# Ver1_4.net
KiCad netlist of a schematic drawn in Altium Designer
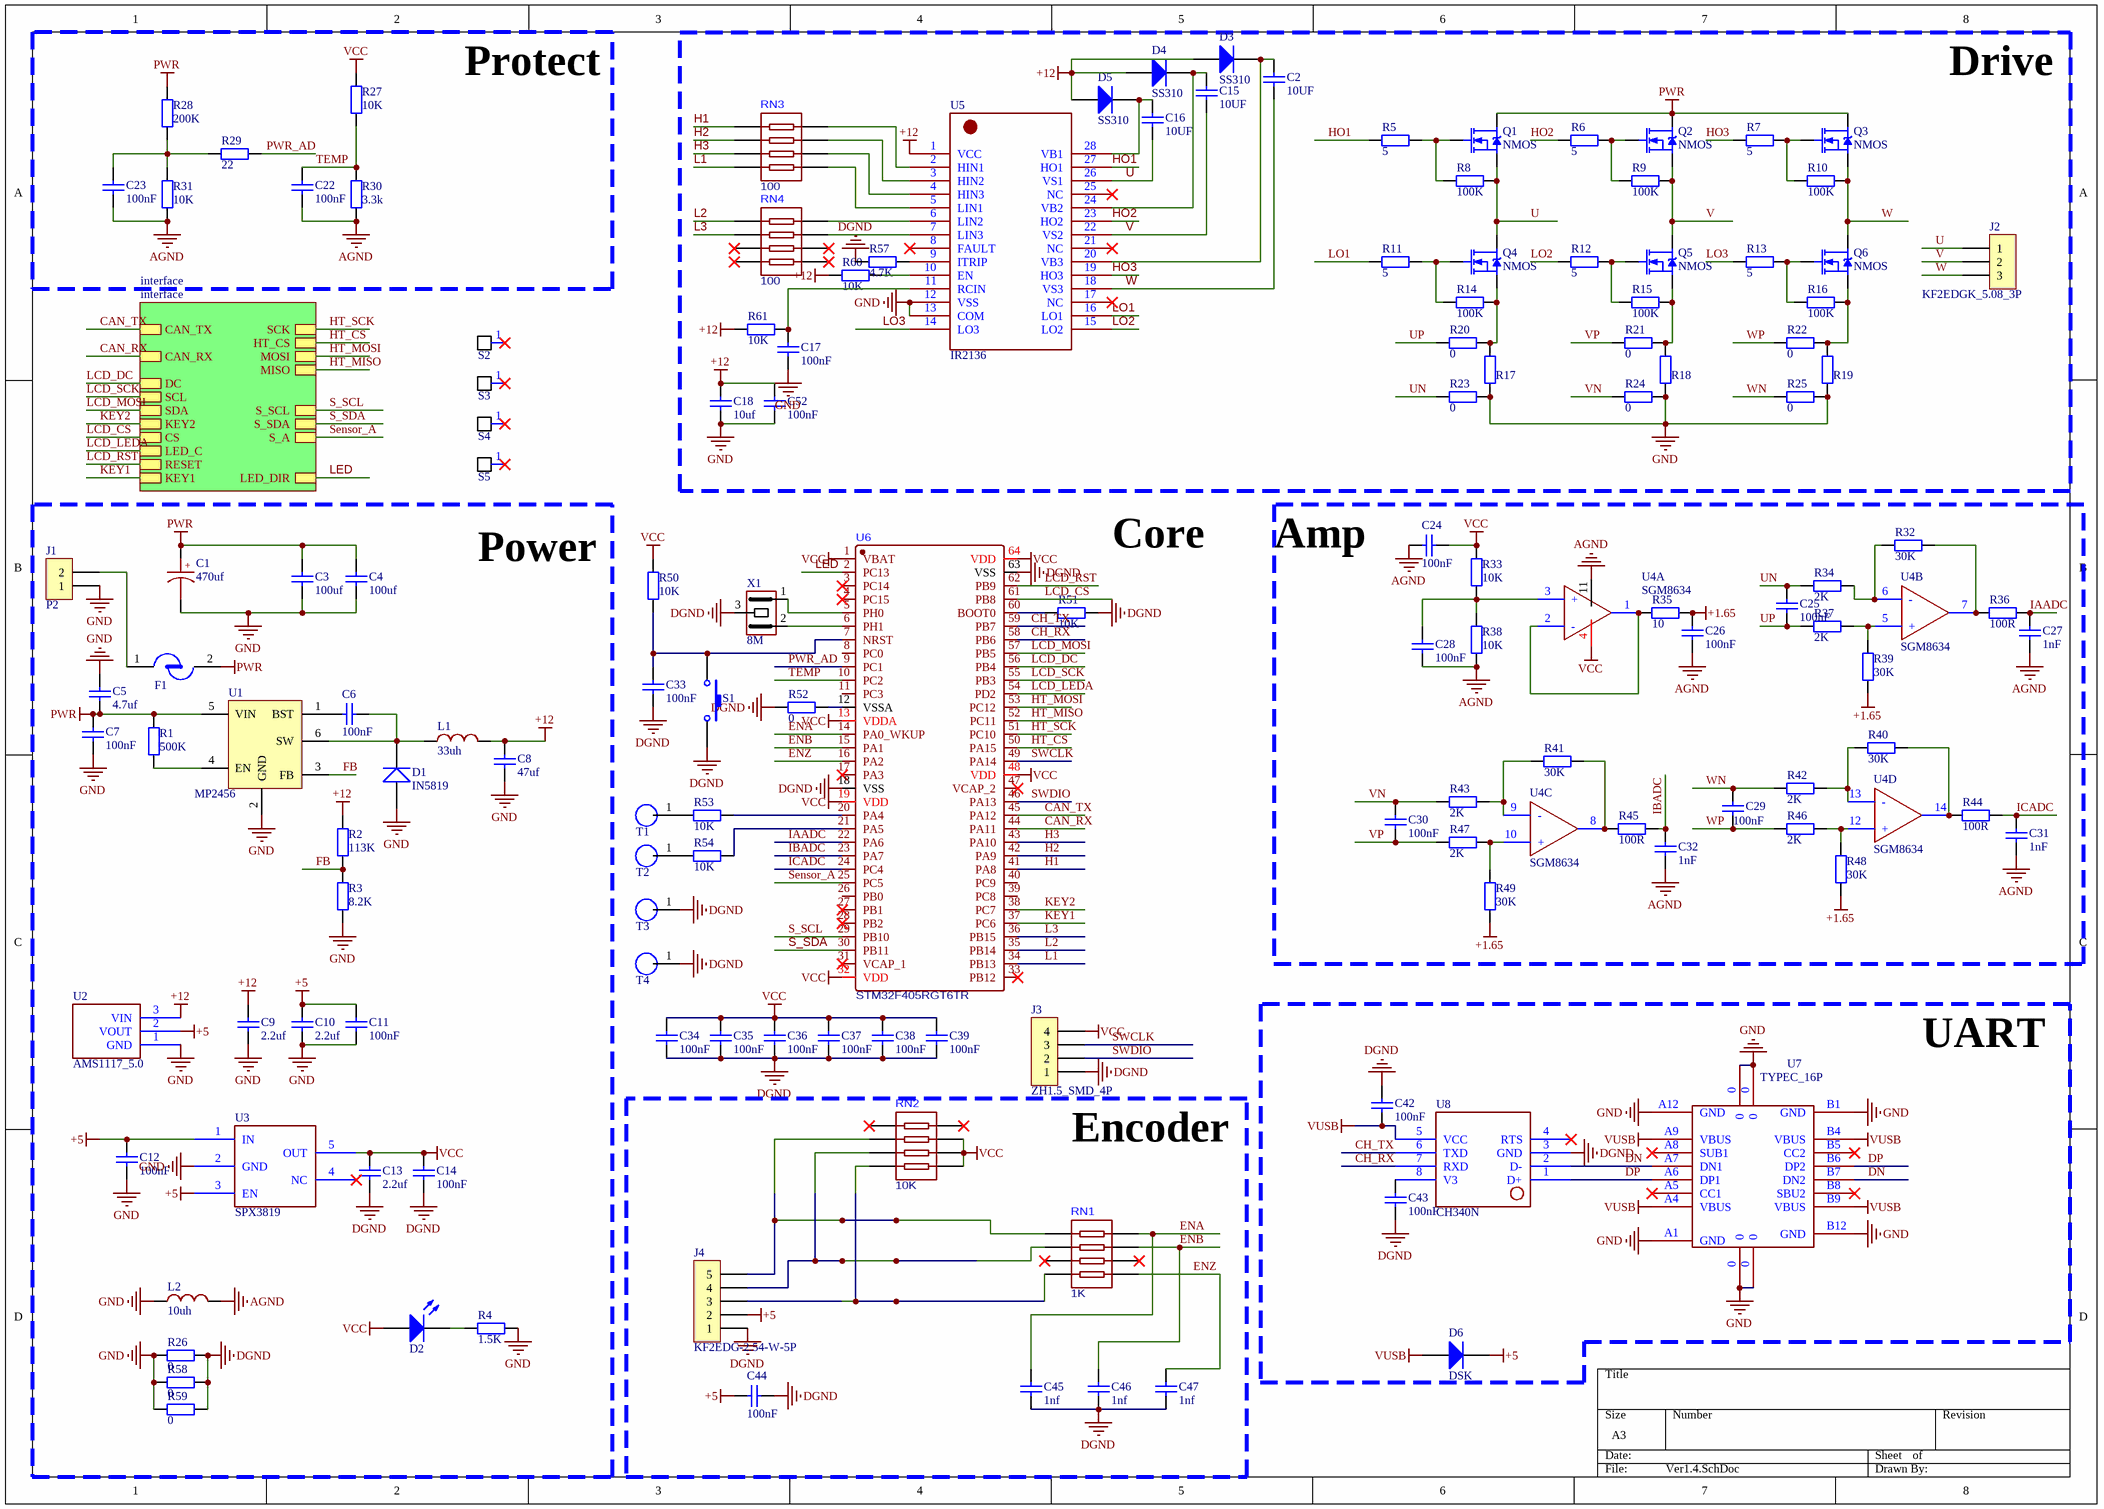
[diagram p0: Ver1.4.SchDoc]

(export (version "E")
  (design (tool "Eeschema 10.0.6"))
  (components
    (comp (ref "C1")
      (value "470uf")
      (footprint "CAP 5.0*12.5*20-H - BK")
      (description "CAP TH 330uf 13*25")
      (libsource (lib "CAP") (part "CAP_TH_D13"))
    )
    (comp (ref "C2")
      (value "10UF")
      (footprint "C 0603")
      (description "无极性电容")
      (fields (field (name "Comment") "Cap") (field (name "PUBLISHER") "Altium Limited"))
      (libsource (lib "CAP") (part "C0603"))
    )
    (comp (ref "C3")
      (value "100uf")
      (footprint "C 1210_L")
      (description "无极性电容")
      (fields (field (name "Comment") "Cap") (field (name "PUBLISHER") "Altium Limited"))
      (libsource (lib "CAP") (part "C1210"))
    )
    (comp (ref "C4")
      (value "100uf")
      (footprint "C 1210_L")
      (description "无极性电容")
      (fields (field (name "Comment") "Cap") (field (name "PUBLISHER") "Altium Limited"))
      (libsource (lib "CAP") (part "C1210"))
    )
    (comp (ref "C5")
      (value "4.7uf")
      (footprint "C 0402_L")
      (description "无极性电容")
      (fields (field (name "Comment") "Cap") (field (name "PUBLISHER") "Altium Limited"))
      (libsource (lib "CAP") (part "C0402"))
    )
    (comp (ref "C6")
      (value "100nF")
      (footprint "C 0402_L")
      (description "无极性电容")
      (fields (field (name "Comment") "Cap") (field (name "PUBLISHER") "Altium Limited"))
      (libsource (lib "CAP") (part "C0402"))
    )
    (comp (ref "C7")
      (value "100nF")
      (footprint "C 0402_L")
      (description "无极性电容")
      (fields (field (name "Comment") "Cap") (field (name "PUBLISHER") "Altium Limited"))
      (libsource (lib "CAP") (part "C0402"))
    )
    (comp (ref "C8")
      (value "47uf")
      (footprint "C 1206_L")
      (description "无极性电容")
      (fields (field (name "Comment") "Cap") (field (name "PUBLISHER") "Altium Limited"))
      (libsource (lib "CAP") (part "C1206"))
    )
    (comp (ref "C9")
      (value "2.2uf")
      (footprint "C 0402_L")
      (description "无极性电容")
      (fields (field (name "Comment") "Cap") (field (name "PUBLISHER") "Altium Limited"))
      (libsource (lib "CAP") (part "C0402"))
    )
    (comp (ref "C10")
      (value "2.2uf")
      (footprint "C 0402_L")
      (description "无极性电容")
      (fields (field (name "Comment") "Cap") (field (name "PUBLISHER") "Altium Limited"))
      (libsource (lib "CAP") (part "C0402"))
    )
    (comp (ref "C11")
      (value "100nF")
      (footprint "C 0402_L")
      (description "无极性电容")
      (fields (field (name "Comment") "Cap") (field (name "PUBLISHER") "Altium Limited"))
      (libsource (lib "CAP") (part "C0402"))
    )
    (comp (ref "C12")
      (value "100nF")
      (footprint "C 0402_L")
      (description "无极性电容")
      (fields (field (name "Comment") "Cap") (field (name "PUBLISHER") "Altium Limited"))
      (libsource (lib "CAP") (part "C0402"))
    )
    (comp (ref "C13")
      (value "2.2uf")
      (footprint "C 0402_L")
      (description "无极性电容")
      (fields (field (name "Comment") "Cap") (field (name "PUBLISHER") "Altium Limited"))
      (libsource (lib "CAP") (part "C0402"))
    )
    (comp (ref "C14")
      (value "100nF")
      (footprint "C 0402_L")
      (description "无极性电容")
      (fields (field (name "Comment") "Cap") (field (name "PUBLISHER") "Altium Limited"))
      (libsource (lib "CAP") (part "C0402"))
    )
    (comp (ref "C15")
      (value "10UF")
      (footprint "C 0603")
      (description "无极性电容")
      (fields (field (name "Comment") "Cap") (field (name "PUBLISHER") "Altium Limited"))
      (libsource (lib "CAP") (part "C0603"))
    )
    (comp (ref "C16")
      (value "10UF")
      (footprint "C 0603")
      (description "无极性电容")
      (fields (field (name "Comment") "Cap") (field (name "PUBLISHER") "Altium Limited"))
      (libsource (lib "CAP") (part "C0603"))
    )
    (comp (ref "C17")
      (value "100nF")
      (footprint "C 0402_L")
      (description "无极性电容")
      (fields (field (name "Comment") "Cap") (field (name "PUBLISHER") "Altium Limited"))
      (libsource (lib "CAP") (part "C0402"))
    )
    (comp (ref "C18")
      (value "10uf")
      (footprint "C 0603")
      (description "无极性电容")
      (fields (field (name "Comment") "Cap") (field (name "PUBLISHER") "Altium Limited"))
      (libsource (lib "CAP") (part "C0603"))
    )
    (comp (ref "C22")
      (value "100nF")
      (footprint "C 0402_L")
      (description "无极性电容")
      (fields (field (name "Comment") "Cap") (field (name "PUBLISHER") "Altium Limited"))
      (libsource (lib "CAP") (part "C0402"))
    )
    (comp (ref "C23")
      (value "100nF")
      (footprint "C 0402_L")
      (description "无极性电容")
      (fields (field (name "Comment") "Cap") (field (name "PUBLISHER") "Altium Limited"))
      (libsource (lib "CAP") (part "C0402"))
    )
    (comp (ref "C24")
      (value "100nF")
      (footprint "C 0402_L")
      (description "无极性电容")
      (fields (field (name "Comment") "Cap") (field (name "PUBLISHER") "Altium Limited"))
      (libsource (lib "CAP") (part "C0402"))
    )
    (comp (ref "C25")
      (value "100nF")
      (footprint "C 0402_L")
      (description "无极性电容")
      (fields (field (name "Comment") "Cap") (field (name "PUBLISHER") "Altium Limited"))
      (libsource (lib "CAP") (part "C0402"))
    )
    (comp (ref "C26")
      (value "100nF")
      (footprint "C 0402_L")
      (description "无极性电容")
      (fields (field (name "Comment") "Cap") (field (name "PUBLISHER") "Altium Limited"))
      (libsource (lib "CAP") (part "C0402"))
    )
    (comp (ref "C27")
      (value "1nF")
      (footprint "C 0402_L")
      (description "无极性电容")
      (fields (field (name "Comment") "Cap") (field (name "PUBLISHER") "Altium Limited"))
      (libsource (lib "CAP") (part "C0402"))
    )
    (comp (ref "C28")
      (value "100nF")
      (footprint "C 0402_L")
      (description "无极性电容")
      (fields (field (name "Comment") "Cap") (field (name "PUBLISHER") "Altium Limited"))
      (libsource (lib "CAP") (part "C0402"))
    )
    (comp (ref "C29")
      (value "100nF")
      (footprint "C 0402_L")
      (description "无极性电容")
      (fields (field (name "Comment") "Cap") (field (name "PUBLISHER") "Altium Limited"))
      (libsource (lib "CAP") (part "C0402"))
    )
    (comp (ref "C30")
      (value "100nF")
      (footprint "C 0402_L")
      (description "无极性电容")
      (fields (field (name "Comment") "Cap") (field (name "PUBLISHER") "Altium Limited"))
      (libsource (lib "CAP") (part "C0402"))
    )
    (comp (ref "C31")
      (value "1nF")
      (footprint "C 0402_L")
      (description "无极性电容")
      (fields (field (name "Comment") "Cap") (field (name "PUBLISHER") "Altium Limited"))
      (libsource (lib "CAP") (part "C0402"))
    )
    (comp (ref "C32")
      (value "1nF")
      (footprint "C 0402_L")
      (description "无极性电容")
      (fields (field (name "Comment") "Cap") (field (name "PUBLISHER") "Altium Limited"))
      (libsource (lib "CAP") (part "C0402"))
    )
    (comp (ref "C33")
      (value "100nF")
      (footprint "C 0402_L")
      (description "无极性电容")
      (fields (field (name "Comment") "Cap") (field (name "PUBLISHER") "Altium Limited"))
      (libsource (lib "CAP") (part "C0402"))
    )
    (comp (ref "C34")
      (value "100nF")
      (footprint "C 0402_L")
      (description "无极性电容")
      (fields (field (name "Comment") "Cap") (field (name "PUBLISHER") "Altium Limited"))
      (libsource (lib "CAP") (part "C0402"))
    )
    (comp (ref "C35")
      (value "100nF")
      (footprint "C 0402_L")
      (description "无极性电容")
      (fields (field (name "Comment") "Cap") (field (name "PUBLISHER") "Altium Limited"))
      (libsource (lib "CAP") (part "C0402"))
    )
    (comp (ref "C36")
      (value "100nF")
      (footprint "C 0402_L")
      (description "无极性电容")
      (fields (field (name "Comment") "Cap") (field (name "PUBLISHER") "Altium Limited"))
      (libsource (lib "CAP") (part "C0402"))
    )
    (comp (ref "C37")
      (value "100nF")
      (footprint "C 0402_L")
      (description "无极性电容")
      (fields (field (name "Comment") "Cap") (field (name "PUBLISHER") "Altium Limited"))
      (libsource (lib "CAP") (part "C0402"))
    )
    (comp (ref "C38")
      (value "100nF")
      (footprint "C 0402_L")
      (description "无极性电容")
      (fields (field (name "Comment") "Cap") (field (name "PUBLISHER") "Altium Limited"))
      (libsource (lib "CAP") (part "C0402"))
    )
    (comp (ref "C39")
      (value "100nF")
      (footprint "C 0402_L")
      (description "无极性电容")
      (fields (field (name "Comment") "Cap") (field (name "PUBLISHER") "Altium Limited"))
      (libsource (lib "CAP") (part "C0402"))
    )
    (comp (ref "C42")
      (value "100nF")
      (footprint "C 0402_L")
      (description "无极性电容")
      (fields (field (name "Comment") "Cap") (field (name "PUBLISHER") "Altium Limited"))
      (libsource (lib "CAP") (part "C0402"))
    )
    (comp (ref "C43")
      (value "100nF")
      (footprint "C 0402_L")
      (description "无极性电容")
      (fields (field (name "Comment") "Cap") (field (name "PUBLISHER") "Altium Limited"))
      (libsource (lib "CAP") (part "C0402"))
    )
    (comp (ref "C44")
      (value "100nF")
      (footprint "C 0402_L")
      (description "无极性电容")
      (fields (field (name "Comment") "Cap") (field (name "PUBLISHER") "Altium Limited"))
      (libsource (lib "CAP") (part "C0402"))
    )
    (comp (ref "C45")
      (value "1nf")
      (footprint "C 0402_L")
      (description "无极性电容")
      (fields (field (name "Comment") "Cap") (field (name "PUBLISHER") "Altium Limited"))
      (libsource (lib "CAP") (part "C0402"))
    )
    (comp (ref "C46")
      (value "1nf")
      (footprint "C 0402_L")
      (description "无极性电容")
      (fields (field (name "Comment") "Cap") (field (name "PUBLISHER") "Altium Limited"))
      (libsource (lib "CAP") (part "C0402"))
    )
    (comp (ref "C47")
      (value "1nf")
      (footprint "C 0402_L")
      (description "无极性电容")
      (fields (field (name "Comment") "Cap") (field (name "PUBLISHER") "Altium Limited"))
      (libsource (lib "CAP") (part "C0402"))
    )
    (comp (ref "C52")
      (value "100nF")
      (footprint "C 0402_L")
      (description "无极性电容")
      (fields (field (name "Comment") "Cap") (field (name "PUBLISHER") "Altium Limited"))
      (libsource (lib "CAP") (part "C0402"))
    )
    (comp (ref "D1")
      (value "IN5819")
      (footprint "SOD-323-12")
      (description "IN系列贴片")
      (fields (field (name "PUBLISHER") "mazhongwei"))
      (libsource (lib "晶体管") (part "DIO_SOD323"))
    )
    (comp (ref "D2")
      (value "LED")
      (footprint "LED0402-R-RD")
      (description "发光二极管")
      (fields (field (name "PUBLISHER") "Altium Limited"))
      (libsource (lib "晶体管") (part "LED0402"))
    )
    (comp (ref "D3")
      (value "SS310")
      (footprint "SMA/12")
      (description "SS系列")
      (fields (field (name "PUBLISHER") "mazhongwei"))
      (libsource (lib "晶体管") (part "DIO_SMA"))
    )
    (comp (ref "D4")
      (value "SS310")
      (footprint "SMA/12")
      (description "SS系列")
      (fields (field (name "PUBLISHER") "mazhongwei"))
      (libsource (lib "晶体管") (part "DIO_SMA"))
    )
    (comp (ref "D5")
      (value "SS310")
      (footprint "SMA/12")
      (description "SS系列")
      (fields (field (name "PUBLISHER") "mazhongwei"))
      (libsource (lib "晶体管") (part "DIO_SMA"))
    )
    (comp (ref "D6")
      (value "DSK")
      (footprint "SOD-123-PIN12")
      (description "DSK系列")
      (fields (field (name "PUBLISHER") "mazhongwei"))
      (libsource (lib "晶体管") (part "DIO_SOD123"))
    )
    (comp (ref "F1") (value "F0603") (footprint "FUSE-BLX-A") (libsource (lib "保险丝") (part "F0603")))
    (comp (ref "J1")
      (value "P2")
      (footprint "KF2EDGK5.08W-2P")
      (description "直插")
      (libsource (lib "接插件") (part "KF2EDGK_5.08_2P"))
    )
    (comp (ref "J2")
      (value "KF2EDGK_5.08_3P")
      (footprint "KF2EDGK5.08W-3P")
      (libsource (lib "接插件") (part "KF2EDGK_5.08_3P"))
    )
    (comp (ref "J3")
      (value "ZH1.5_SMD_4P")
      (footprint "ZH1.5-WS-4P")
      (libsource (lib "接插件") (part "ZH1.5_SMD_4P"))
    )
    (comp (ref "J4")
      (value "KF2EDG-2.54-W-5P")
      (footprint "KF2EDGK-2.54W-5P")
      (libsource (lib "接插件") (part "KF2EDG-2.54-W-5P"))
    )
    (comp (ref "L1")
      (value "33uh")
      (footprint "CD32")
      (description "功率贴片电感")
      (fields (field (name "PUBLISHER") "Altium Limited"))
      (libsource (lib "电感") (part "L0402"))
    )
    (comp (ref "L2")
      (value "10uh")
      (footprint "L 0805")
      (description "功率贴片电感")
      (fields (field (name "PUBLISHER") "Altium Limited"))
      (libsource (lib "电感") (part "L0402"))
    )
    (comp (ref "Q1")
      (value "NMOS")
      (footprint "TO252")
      (description "N沟道场效应管")
      (libsource (lib "晶体管") (part "NMOS"))
    )
    (comp (ref "Q2")
      (value "NMOS")
      (footprint "TO252")
      (description "N沟道场效应管")
      (libsource (lib "晶体管") (part "NMOS"))
    )
    (comp (ref "Q3")
      (value "NMOS")
      (footprint "TO252")
      (description "N沟道场效应管")
      (libsource (lib "晶体管") (part "NMOS"))
    )
    (comp (ref "Q4")
      (value "NMOS")
      (footprint "TO252")
      (description "N沟道场效应管")
      (libsource (lib "晶体管") (part "NMOS"))
    )
    (comp (ref "Q5")
      (value "NMOS")
      (footprint "TO252")
      (description "N沟道场效应管")
      (libsource (lib "晶体管") (part "NMOS"))
    )
    (comp (ref "Q6")
      (value "NMOS")
      (footprint "TO252")
      (description "N沟道场效应管")
      (libsource (lib "晶体管") (part "NMOS"))
    )
    (comp (ref "R1")
      (value "500K")
      (footprint "0402R")
      (description "贴片电阻")
      (fields (field (name "Comment") "Res1") (field (name "PUBLISHER") "Altium Limited"))
      (libsource (lib "") (part "R0402_1"))
    )
    (comp (ref "R2")
      (value "113K")
      (footprint "0402R")
      (description "贴片电阻")
      (fields (field (name "Comment") "Res1") (field (name "PUBLISHER") "Altium Limited"))
      (libsource (lib "") (part "R0402_1"))
    )
    (comp (ref "R3")
      (value "8.2K")
      (footprint "0402R")
      (description "贴片电阻")
      (fields (field (name "Comment") "Res1") (field (name "PUBLISHER") "Altium Limited"))
      (libsource (lib "") (part "R0402_1"))
    )
    (comp (ref "R4")
      (value "1.5K")
      (footprint "0402R")
      (description "贴片电阻")
      (fields (field (name "Comment") "Res1") (field (name "PUBLISHER") "Altium Limited"))
      (libsource (lib "RES") (part "R0402"))
    )
    (comp (ref "R5")
      (value "5")
      (footprint "0402R")
      (description "贴片电阻")
      (fields (field (name "Comment") "Res1") (field (name "PUBLISHER") "Altium Limited"))
      (libsource (lib "RES") (part "R0402"))
    )
    (comp (ref "R6")
      (value "5")
      (footprint "0402R")
      (description "贴片电阻")
      (fields (field (name "Comment") "Res1") (field (name "PUBLISHER") "Altium Limited"))
      (libsource (lib "RES") (part "R0402"))
    )
    (comp (ref "R7")
      (value "5")
      (footprint "0402R")
      (description "贴片电阻")
      (fields (field (name "Comment") "Res1") (field (name "PUBLISHER") "Altium Limited"))
      (libsource (lib "RES") (part "R0402"))
    )
    (comp (ref "R8")
      (value "100K")
      (footprint "0402R")
      (description "贴片电阻")
      (fields (field (name "Comment") "Res1") (field (name "PUBLISHER") "Altium Limited"))
      (libsource (lib "RES") (part "R0402"))
    )
    (comp (ref "R9")
      (value "100K")
      (footprint "0402R")
      (description "贴片电阻")
      (fields (field (name "Comment") "Res1") (field (name "PUBLISHER") "Altium Limited"))
      (libsource (lib "RES") (part "R0402"))
    )
    (comp (ref "R10")
      (value "100K")
      (footprint "0402R")
      (description "贴片电阻")
      (fields (field (name "Comment") "Res1") (field (name "PUBLISHER") "Altium Limited"))
      (libsource (lib "RES") (part "R0402"))
    )
    (comp (ref "R11")
      (value "5")
      (footprint "0402R")
      (description "贴片电阻")
      (fields (field (name "Comment") "Res1") (field (name "PUBLISHER") "Altium Limited"))
      (libsource (lib "RES") (part "R0402"))
    )
    (comp (ref "R12")
      (value "5")
      (footprint "0402R")
      (description "贴片电阻")
      (fields (field (name "Comment") "Res1") (field (name "PUBLISHER") "Altium Limited"))
      (libsource (lib "RES") (part "R0402"))
    )
    (comp (ref "R13")
      (value "5")
      (footprint "0402R")
      (description "贴片电阻")
      (fields (field (name "Comment") "Res1") (field (name "PUBLISHER") "Altium Limited"))
      (libsource (lib "RES") (part "R0402"))
    )
    (comp (ref "R14")
      (value "100K")
      (footprint "0402R")
      (description "贴片电阻")
      (fields (field (name "Comment") "Res1") (field (name "PUBLISHER") "Altium Limited"))
      (libsource (lib "RES") (part "R0402"))
    )
    (comp (ref "R15")
      (value "100K")
      (footprint "0402R")
      (description "贴片电阻")
      (fields (field (name "Comment") "Res1") (field (name "PUBLISHER") "Altium Limited"))
      (libsource (lib "RES") (part "R0402"))
    )
    (comp (ref "R16")
      (value "100K")
      (footprint "0402R")
      (description "贴片电阻")
      (fields (field (name "Comment") "Res1") (field (name "PUBLISHER") "Altium Limited"))
      (libsource (lib "RES") (part "R0402"))
    )
    (comp (ref "R17")
      (value "0.01")
      (footprint "2512R")
      (description "0.01采样电阻3W")
      (fields (field (name "PUBLISHER") "Altium Limited"))
      (libsource (lib "RES") (part "R2512"))
    )
    (comp (ref "R18")
      (value "0.01")
      (footprint "2512R")
      (description "0.01采样电阻3W")
      (fields (field (name "PUBLISHER") "Altium Limited"))
      (libsource (lib "RES") (part "R2512"))
    )
    (comp (ref "R19")
      (value "0.01")
      (footprint "2512R")
      (description "0.01采样电阻3W")
      (fields (field (name "PUBLISHER") "Altium Limited"))
      (libsource (lib "RES") (part "R2512"))
    )
    (comp (ref "R20")
      (value "0")
      (footprint "0402R")
      (description "贴片电阻")
      (fields (field (name "Comment") "Res1") (field (name "PUBLISHER") "Altium Limited"))
      (libsource (lib "RES") (part "R0402"))
    )
    (comp (ref "R21")
      (value "0")
      (footprint "0402R")
      (description "贴片电阻")
      (fields (field (name "Comment") "Res1") (field (name "PUBLISHER") "Altium Limited"))
      (libsource (lib "RES") (part "R0402"))
    )
    (comp (ref "R22")
      (value "0")
      (footprint "0402R")
      (description "贴片电阻")
      (fields (field (name "Comment") "Res1") (field (name "PUBLISHER") "Altium Limited"))
      (libsource (lib "RES") (part "R0402"))
    )
    (comp (ref "R23")
      (value "0")
      (footprint "0402R")
      (description "贴片电阻")
      (fields (field (name "Comment") "Res1") (field (name "PUBLISHER") "Altium Limited"))
      (libsource (lib "RES") (part "R0402"))
    )
    (comp (ref "R24")
      (value "0")
      (footprint "0402R")
      (description "贴片电阻")
      (fields (field (name "Comment") "Res1") (field (name "PUBLISHER") "Altium Limited"))
      (libsource (lib "RES") (part "R0402"))
    )
    (comp (ref "R25")
      (value "0")
      (footprint "0402R")
      (description "贴片电阻")
      (fields (field (name "Comment") "Res1") (field (name "PUBLISHER") "Altium Limited"))
      (libsource (lib "RES") (part "R0402"))
    )
    (comp (ref "R26")
      (value "0")
      (footprint "0402R")
      (description "贴片电阻")
      (fields (field (name "Comment") "Res1") (field (name "PUBLISHER") "Altium Limited"))
      (libsource (lib "RES") (part "R0402"))
    )
    (comp (ref "R27")
      (value "10K")
      (footprint "0402R")
      (description "贴片电阻")
      (fields (field (name "Comment") "Res1") (field (name "PUBLISHER") "Altium Limited"))
      (libsource (lib "") (part "R0402_1"))
    )
    (comp (ref "R28")
      (value "200K")
      (footprint "0402R")
      (description "贴片电阻")
      (fields (field (name "Comment") "Res1") (field (name "PUBLISHER") "Altium Limited"))
      (libsource (lib "") (part "R0402_1"))
    )
    (comp (ref "R29")
      (value "22")
      (footprint "0402R")
      (description "贴片电阻")
      (fields (field (name "Comment") "Res1") (field (name "PUBLISHER") "Altium Limited"))
      (libsource (lib "RES") (part "R0402"))
    )
    (comp (ref "R30")
      (value "3.3k")
      (footprint "0402R")
      (description "贴片电阻")
      (fields (field (name "Comment") "Res1") (field (name "PUBLISHER") "Altium Limited"))
      (libsource (lib "") (part "R0402_1"))
    )
    (comp (ref "R31")
      (value "10K")
      (footprint "0402R")
      (description "贴片电阻")
      (fields (field (name "Comment") "Res1") (field (name "PUBLISHER") "Altium Limited"))
      (libsource (lib "") (part "R0402_1"))
    )
    (comp (ref "R32")
      (value "30K")
      (footprint "0402R")
      (description "贴片电阻")
      (fields (field (name "Comment") "Res1") (field (name "PUBLISHER") "Altium Limited"))
      (libsource (lib "") (part "R0402_2"))
    )
    (comp (ref "R33")
      (value "10K")
      (footprint "0402R")
      (description "贴片电阻")
      (fields (field (name "Comment") "Res1") (field (name "PUBLISHER") "Altium Limited"))
      (libsource (lib "") (part "R0402_3"))
    )
    (comp (ref "R34")
      (value "2K")
      (footprint "0402R")
      (description "贴片电阻")
      (fields (field (name "Comment") "Res1") (field (name "PUBLISHER") "Altium Limited"))
      (libsource (lib "RES") (part "R0402"))
    )
    (comp (ref "R35")
      (value "10")
      (footprint "0402R")
      (description "贴片电阻")
      (fields (field (name "Comment") "Res1") (field (name "PUBLISHER") "Altium Limited"))
      (libsource (lib "RES") (part "R0402"))
    )
    (comp (ref "R36")
      (value "100R")
      (footprint "0402R")
      (description "贴片电阻")
      (fields (field (name "Comment") "Res1") (field (name "PUBLISHER") "Altium Limited"))
      (libsource (lib "") (part "R0402_2"))
    )
    (comp (ref "R37")
      (value "2K")
      (footprint "0402R")
      (description "贴片电阻")
      (fields (field (name "Comment") "Res1") (field (name "PUBLISHER") "Altium Limited"))
      (libsource (lib "RES") (part "R0402"))
    )
    (comp (ref "R38")
      (value "10K")
      (footprint "0402R")
      (description "贴片电阻")
      (fields (field (name "Comment") "Res1") (field (name "PUBLISHER") "Altium Limited"))
      (libsource (lib "") (part "R0402_3"))
    )
    (comp (ref "R39")
      (value "30K")
      (footprint "0402R")
      (description "贴片电阻")
      (fields (field (name "Comment") "Res1") (field (name "PUBLISHER") "Altium Limited"))
      (libsource (lib "") (part "R0402_1"))
    )
    (comp (ref "R40")
      (value "30K")
      (footprint "0402R")
      (description "贴片电阻")
      (fields (field (name "Comment") "Res1") (field (name "PUBLISHER") "Altium Limited"))
      (libsource (lib "") (part "R0402_2"))
    )
    (comp (ref "R41")
      (value "30K")
      (footprint "0402R")
      (description "贴片电阻")
      (fields (field (name "Comment") "Res1") (field (name "PUBLISHER") "Altium Limited"))
      (libsource (lib "") (part "R0402_2"))
    )
    (comp (ref "R42")
      (value "2K")
      (footprint "0402R")
      (description "贴片电阻")
      (fields (field (name "Comment") "Res1") (field (name "PUBLISHER") "Altium Limited"))
      (libsource (lib "RES") (part "R0402"))
    )
    (comp (ref "R43")
      (value "2K")
      (footprint "0402R")
      (description "贴片电阻")
      (fields (field (name "Comment") "Res1") (field (name "PUBLISHER") "Altium Limited"))
      (libsource (lib "RES") (part "R0402"))
    )
    (comp (ref "R44")
      (value "100R")
      (footprint "0402R")
      (description "贴片电阻")
      (fields (field (name "Comment") "Res1") (field (name "PUBLISHER") "Altium Limited"))
      (libsource (lib "") (part "R0402_2"))
    )
    (comp (ref "R45")
      (value "100R")
      (footprint "0402R")
      (description "贴片电阻")
      (fields (field (name "Comment") "Res1") (field (name "PUBLISHER") "Altium Limited"))
      (libsource (lib "") (part "R0402_2"))
    )
    (comp (ref "R46")
      (value "2K")
      (footprint "0402R")
      (description "贴片电阻")
      (fields (field (name "Comment") "Res1") (field (name "PUBLISHER") "Altium Limited"))
      (libsource (lib "RES") (part "R0402"))
    )
    (comp (ref "R47")
      (value "2K")
      (footprint "0402R")
      (description "贴片电阻")
      (fields (field (name "Comment") "Res1") (field (name "PUBLISHER") "Altium Limited"))
      (libsource (lib "RES") (part "R0402"))
    )
    (comp (ref "R48")
      (value "30K")
      (footprint "0402R")
      (description "贴片电阻")
      (fields (field (name "Comment") "Res1") (field (name "PUBLISHER") "Altium Limited"))
      (libsource (lib "") (part "R0402_1"))
    )
    (comp (ref "R49")
      (value "30K")
      (footprint "0402R")
      (description "贴片电阻")
      (fields (field (name "Comment") "Res1") (field (name "PUBLISHER") "Altium Limited"))
      (libsource (lib "") (part "R0402_1"))
    )
    (comp (ref "R50")
      (value "10K")
      (footprint "0402R")
      (description "贴片电阻")
      (fields (field (name "Comment") "Res1") (field (name "PUBLISHER") "Altium Limited"))
      (libsource (lib "") (part "R0402_1"))
    )
    (comp (ref "R51")
      (value "10K")
      (footprint "0402R")
      (description "贴片电阻")
      (fields (field (name "Comment") "Res1") (field (name "PUBLISHER") "Altium Limited"))
      (libsource (lib "RES") (part "R0402"))
    )
    (comp (ref "R52")
      (value "0")
      (footprint "0402R")
      (description "贴片电阻")
      (fields (field (name "Comment") "Res1") (field (name "PUBLISHER") "Altium Limited"))
      (libsource (lib "RES") (part "R0603"))
    )
    (comp (ref "R53")
      (value "10K")
      (footprint "0402R")
      (description "贴片电阻")
      (fields (field (name "Comment") "Res1") (field (name "PUBLISHER") "Altium Limited"))
      (libsource (lib "RES") (part "R0402"))
    )
    (comp (ref "R54")
      (value "10K")
      (footprint "0402R")
      (description "贴片电阻")
      (fields (field (name "Comment") "Res1") (field (name "PUBLISHER") "Altium Limited"))
      (libsource (lib "RES") (part "R0402"))
    )
    (comp (ref "R57")
      (value "4.7K")
      (footprint "0402R")
      (description "贴片电阻")
      (fields (field (name "Comment") "Res1") (field (name "PUBLISHER") "Altium Limited"))
      (libsource (lib "RES") (part "R0402"))
    )
    (comp (ref "R58")
      (value "0")
      (footprint "0402R")
      (description "贴片电阻")
      (fields (field (name "Comment") "Res1") (field (name "PUBLISHER") "Altium Limited"))
      (libsource (lib "RES") (part "R0402"))
    )
    (comp (ref "R59")
      (value "0")
      (footprint "0402R")
      (description "贴片电阻")
      (fields (field (name "Comment") "Res1") (field (name "PUBLISHER") "Altium Limited"))
      (libsource (lib "RES") (part "R0402"))
    )
    (comp (ref "R60")
      (value "10K")
      (footprint "0402R")
      (description "贴片电阻")
      (fields (field (name "Comment") "Res1") (field (name "PUBLISHER") "Altium Limited"))
      (libsource (lib "") (part "R0402_2"))
    )
    (comp (ref "R61")
      (value "10K")
      (footprint "0402R")
      (description "贴片电阻")
      (fields (field (name "Comment") "Res1") (field (name "PUBLISHER") "Altium Limited"))
      (libsource (lib "") (part "R0402_2"))
    )
    (comp (ref "RN1")
      (value "1K")
      (footprint "8P4R-0402")
      (description "0402排阻")
      (libsource (lib "RES") (part "RESP0402"))
    )
    (comp (ref "RN2")
      (value "10K")
      (footprint "8P4R-0402")
      (description "0402排阻")
      (libsource (lib "RES") (part "RESP0402"))
    )
    (comp (ref "RN3")
      (value "100")
      (footprint "8P4R-0402")
      (description "0402排阻")
      (libsource (lib "RES") (part "RESP0402"))
    )
    (comp (ref "RN4")
      (value "100")
      (footprint "8P4R-0402")
      (description "0402排阻")
      (libsource (lib "RES") (part "RESP0402"))
    )
    (comp (ref "S1")
      (value "SW-PB")
      (footprint "SMD-4X4X1.5")
      (description "贴片侧4脚按键")
      (fields (field (name "PUBLISHER") "Altium Limited"))
      (libsource (lib "KEY") (part "KEY_SMD_2*4*3.5"))
    )
    (comp (ref "S2")
      (value "M3")
      (footprint "3mm螺丝孔")
      (description "3mm螺丝孔")
      (libsource (lib "MCU") (part "M3"))
    )
    (comp (ref "S3")
      (value "M3")
      (footprint "3mm螺丝孔")
      (description "3mm螺丝孔")
      (libsource (lib "MCU") (part "M3"))
    )
    (comp (ref "S4")
      (value "M3")
      (footprint "3mm螺丝孔")
      (description "3mm螺丝孔")
      (libsource (lib "MCU") (part "M3"))
    )
    (comp (ref "S5")
      (value "M3")
      (footprint "3mm螺丝孔")
      (description "3mm螺丝孔")
      (libsource (lib "MCU") (part "M3"))
    )
    (comp (ref "T1")
      (value "TEST")
      (footprint "TEST_1mm")
      (description "测试点1mm")
      (libsource (lib "MCU") (part "TEST"))
    )
    (comp (ref "T2")
      (value "TEST")
      (footprint "TEST_1mm")
      (description "测试点1mm")
      (libsource (lib "MCU") (part "TEST"))
    )
    (comp (ref "T3")
      (value "TEST")
      (footprint "TEST_1mm")
      (description "测试点1mm")
      (libsource (lib "MCU") (part "TEST"))
    )
    (comp (ref "T4")
      (value "TEST")
      (footprint "TEST_1mm")
      (description "测试点1mm")
      (libsource (lib "MCU") (part "TEST"))
    )
    (comp (ref "U1") (value "MP2456") (footprint "SOT23-6L") (libsource (lib "MCU") (part "MP2456")))
    (comp (ref "U2")
      (value "AMS1117_5.0")
      (footprint "SOT89_M")
      (description "AMS1117-5V  SOT89   MAX24V")
      (libsource (lib "MCU") (part "AMS1117_5.0"))
    )
    (comp (ref "U3") (value "SPX3819") (footprint "SOT23-5L") (libsource (lib "MCU") (part "SPX3819")))
    (comp (ref "U4")
      (value "SGM8634")
      (footprint "SOP14_L")
      (description "TSSOP-14")
      (libsource (lib "MCU") (part "TL084CPWR"))
    )
    (comp (ref "U5") (value "IR2136") (footprint "SOP28_L") (libsource (lib "MCU") (part "IR2136")))
    (comp (ref "U6")
      (value "STM32F405RGT6TR")
      (footprint "LQFP64 10x10_M")
      (libsource (lib "MCU") (part "STM32F405RGT6TR"))
    )
    (comp (ref "U7") (value "TYPEC_16P") (footprint "TYPECP16") (libsource (lib "MCU") (part "TYPEC_16P")))
    (comp (ref "U8") (value "CH340N") (footprint "SOP8_N") (libsource (lib "MCU") (part "CH340N")))
    (comp (ref "X1")
      (value "8M")
      (footprint "晶振SMD-CSTSE800G52-R0")
      (description "三脚晶振SMD")
      (libsource (lib "MCU") (part "OSC_SMD_3"))
    )
  )
  (nets
    (net (code "1") (name "+1.65") (class "Default")
      (node (ref "C26") (pin "2") (pinfunction "2_2") (pintype "passive"))
      (node (ref "R35") (pin "2") (pinfunction "2_2") (pintype "passive"))
      (node (ref "R39") (pin "1") (pinfunction "1_1") (pintype "passive"))
      (node (ref "R48") (pin "1") (pinfunction "1_1") (pintype "passive"))
      (node (ref "R49") (pin "1") (pinfunction "1_1") (pintype "passive"))
    )
    (net (code "2") (name "+5") (class "Default")
      (node (ref "C10") (pin "2") (pinfunction "2_2") (pintype "passive"))
      (node (ref "C11") (pin "2") (pinfunction "2_2") (pintype "passive"))
      (node (ref "C12") (pin "2") (pinfunction "2_2") (pintype "passive"))
      (node (ref "C44") (pin "2") (pinfunction "2_2") (pintype "passive"))
      (node (ref "D6") (pin "2") (pinfunction "K_2") (pintype "passive"))
      (node (ref "J4") (pin "2") (pinfunction "2_2") (pintype "passive"))
      (node (ref "U2") (pin "2") (pinfunction "VOUT_2") (pintype "passive"))
      (node (ref "U3") (pin "1") (pinfunction "IN_1") (pintype "passive"))
      (node (ref "U3") (pin "3") (pinfunction "EN_3") (pintype "passive"))
    )
    (net (code "3") (name "+12") (class "Default")
      (node (ref "C18") (pin "2") (pinfunction "2_2") (pintype "passive"))
      (node (ref "C52") (pin "2") (pinfunction "2_2") (pintype "passive"))
      (node (ref "C8") (pin "2") (pinfunction "2_2") (pintype "passive"))
      (node (ref "C9") (pin "2") (pinfunction "2_2") (pintype "passive"))
      (node (ref "D3") (pin "1") (pinfunction "A_1") (pintype "passive"))
      (node (ref "D4") (pin "1") (pinfunction "A_1") (pintype "passive"))
      (node (ref "D5") (pin "1") (pinfunction "A_1") (pintype "passive"))
      (node (ref "L1") (pin "2") (pinfunction "2_2") (pintype "passive"))
      (node (ref "R2") (pin "2") (pinfunction "2_2") (pintype "passive"))
      (node (ref "R60") (pin "2") (pinfunction "2_2") (pintype "passive"))
      (node (ref "R61") (pin "2") (pinfunction "2_2") (pintype "passive"))
      (node (ref "U2") (pin "3") (pinfunction "VIN_3") (pintype "passive"))
      (node (ref "U5") (pin "1") (pinfunction "VCC_1") (pintype "passive"))
    )
    (net (code "4") (name "/CAN_RX") (class "Default")
      (node (ref "U6") (pin "44") (pinfunction "PA11_44") (pintype "passive"))
    )
    (net (code "5") (name "/CAN_TX") (class "Default")
      (node (ref "U6") (pin "45") (pinfunction "PA12_45") (pintype "passive"))
    )
    (net (code "6") (name "/CH_RX") (class "Default")
      (node (ref "U6") (pin "58") (pinfunction "PB6_58") (pintype "passive"))
      (node (ref "U8") (pin "7") (pinfunction "RXD_7") (pintype "passive"))
    )
    (net (code "7") (name "/CH_TX") (class "Default")
      (node (ref "U6") (pin "59") (pinfunction "PB7_59") (pintype "passive"))
      (node (ref "U8") (pin "6") (pinfunction "TXD_6") (pintype "passive"))
    )
    (net (code "8") (name "/DN") (class "Default")
      (node (ref "U7") (pin "A7") (pinfunction "DN1_A7") (pintype "passive"))
      (node (ref "U7") (pin "B7") (pinfunction "DN2_B7") (pintype "passive"))
      (node (ref "U8") (pin "2") (pinfunction "D-_2") (pintype "passive"))
    )
    (net (code "9") (name "/DP") (class "Default")
      (node (ref "U7") (pin "A6") (pinfunction "DP1_A6") (pintype "passive"))
      (node (ref "U7") (pin "B6") (pinfunction "DP2_B6") (pintype "passive"))
      (node (ref "U8") (pin "1") (pinfunction "D+_1") (pintype "passive"))
    )
    (net (code "10") (name "/ENA") (class "Default")
      (node (ref "C45") (pin "2") (pinfunction "2_2") (pintype "passive"))
      (node (ref "RN1") (pin "8") (pinfunction "8_8") (pintype "passive"))
      (node (ref "U6") (pin "14") (pinfunction "PA0_WKUP_14") (pintype "passive"))
    )
    (net (code "11") (name "/ENB") (class "Default")
      (node (ref "C46") (pin "2") (pinfunction "2_2") (pintype "passive"))
      (node (ref "RN1") (pin "7") (pinfunction "7_7") (pintype "passive"))
      (node (ref "U6") (pin "15") (pinfunction "PA1_15") (pintype "passive"))
    )
    (net (code "12") (name "/ENZ") (class "Default")
      (node (ref "C47") (pin "2") (pinfunction "2_2") (pintype "passive"))
      (node (ref "RN1") (pin "5") (pinfunction "5_5") (pintype "passive"))
      (node (ref "U6") (pin "16") (pinfunction "PA2_16") (pintype "passive"))
    )
    (net (code "13") (name "/FB") (class "Default")
      (node (ref "R2") (pin "1") (pinfunction "1_1") (pintype "passive"))
      (node (ref "R3") (pin "2") (pinfunction "2_2") (pintype "passive"))
      (node (ref "U1") (pin "3") (pinfunction "FB_3") (pintype "passive"))
    )
    (net (code "14") (name "/H1") (class "Default")
      (node (ref "RN3") (pin "5") (pinfunction "5_5") (pintype "passive"))
      (node (ref "U6") (pin "41") (pinfunction "PA8_41") (pintype "passive"))
    )
    (net (code "15") (name "/H2") (class "Default")
      (node (ref "RN3") (pin "6") (pinfunction "6_6") (pintype "passive"))
      (node (ref "U6") (pin "42") (pinfunction "PA9_42") (pintype "passive"))
    )
    (net (code "16") (name "/H3") (class "Default")
      (node (ref "RN3") (pin "7") (pinfunction "7_7") (pintype "passive"))
      (node (ref "U6") (pin "43") (pinfunction "PA10_43") (pintype "passive"))
    )
    (net (code "17") (name "/HO1") (class "Default")
      (node (ref "R5") (pin "1") (pinfunction "1_1") (pintype "passive"))
      (node (ref "U5") (pin "27") (pinfunction "HO1_27") (pintype "passive"))
    )
    (net (code "18") (name "/HO2") (class "Default")
      (node (ref "R6") (pin "1") (pinfunction "1_1") (pintype "passive"))
      (node (ref "U5") (pin "23") (pinfunction "HO2_23") (pintype "passive"))
    )
    (net (code "19") (name "/HO3") (class "Default")
      (node (ref "R7") (pin "1") (pinfunction "1_1") (pintype "passive"))
      (node (ref "U5") (pin "19") (pinfunction "HO3_19") (pintype "passive"))
    )
    (net (code "20") (name "/HT_CS") (class "Default")
      (node (ref "U6") (pin "50") (pinfunction "PA15_50") (pintype "passive"))
    )
    (net (code "21") (name "/HT_MISO") (class "Default")
      (node (ref "U6") (pin "52") (pinfunction "PC11_52") (pintype "passive"))
    )
    (net (code "22") (name "/HT_MOSI") (class "Default")
      (node (ref "U6") (pin "53") (pinfunction "PC12_53") (pintype "passive"))
    )
    (net (code "23") (name "/HT_SCK") (class "Default")
      (node (ref "U6") (pin "51") (pinfunction "PC10_51") (pintype "passive"))
    )
    (net (code "24") (name "/IAADC") (class "Default")
      (node (ref "C27") (pin "2") (pinfunction "2_2") (pintype "passive"))
      (node (ref "R36") (pin "1") (pinfunction "1_1") (pintype "passive"))
      (node (ref "U6") (pin "22") (pinfunction "PA6_22") (pintype "passive"))
    )
    (net (code "25") (name "/IBADC") (class "Default")
      (node (ref "C32") (pin "2") (pinfunction "2_2") (pintype "passive"))
      (node (ref "R45") (pin "1") (pinfunction "1_1") (pintype "passive"))
      (node (ref "U6") (pin "23") (pinfunction "PA7_23") (pintype "passive"))
    )
    (net (code "26") (name "/ICADC") (class "Default")
      (node (ref "C31") (pin "2") (pinfunction "2_2") (pintype "passive"))
      (node (ref "R44") (pin "1") (pinfunction "1_1") (pintype "passive"))
      (node (ref "U6") (pin "24") (pinfunction "PC4_24") (pintype "passive"))
    )
    (net (code "27") (name "/KEY1") (class "Default")
      (node (ref "U6") (pin "37") (pinfunction "PC6_37") (pintype "passive"))
    )
    (net (code "28") (name "/KEY2") (class "Default")
      (node (ref "U6") (pin "38") (pinfunction "PC7_38") (pintype "passive"))
    )
    (net (code "29") (name "/L1") (class "Default")
      (node (ref "RN3") (pin "8") (pinfunction "8_8") (pintype "passive"))
      (node (ref "U6") (pin "34") (pinfunction "PB13_34") (pintype "passive"))
    )
    (net (code "30") (name "/L2") (class "Default")
      (node (ref "RN4") (pin "5") (pinfunction "5_5") (pintype "passive"))
      (node (ref "U6") (pin "35") (pinfunction "PB14_35") (pintype "passive"))
    )
    (net (code "31") (name "/L3") (class "Default")
      (node (ref "RN4") (pin "6") (pinfunction "6_6") (pintype "passive"))
      (node (ref "U6") (pin "36") (pinfunction "PB15_36") (pintype "passive"))
    )
    (net (code "32") (name "/LCD_CS") (class "Default")
      (node (ref "U6") (pin "61") (pinfunction "PB8_61") (pintype "passive"))
    )
    (net (code "33") (name "/LCD_DC") (class "Default")
      (node (ref "U6") (pin "56") (pinfunction "PB4_56") (pintype "passive"))
    )
    (net (code "34") (name "/LCD_LEDA") (class "Default")
      (node (ref "U6") (pin "54") (pinfunction "PD2_54") (pintype "passive"))
    )
    (net (code "35") (name "/LCD_MOSI") (class "Default")
      (node (ref "U6") (pin "57") (pinfunction "PB5_57") (pintype "passive"))
    )
    (net (code "36") (name "/LCD_RST") (class "Default")
      (node (ref "U6") (pin "62") (pinfunction "PB9_62") (pintype "passive"))
    )
    (net (code "37") (name "/LCD_SCK") (class "Default")
      (node (ref "U6") (pin "55") (pinfunction "PB3_55") (pintype "passive"))
    )
    (net (code "38") (name "/LED") (class "Default")
      (node (ref "U6") (pin "2") (pinfunction "PC13_2") (pintype "passive"))
    )
    (net (code "39") (name "/LO1") (class "Default")
      (node (ref "R11") (pin "1") (pinfunction "1_1") (pintype "passive"))
      (node (ref "U5") (pin "16") (pinfunction "LO1_16") (pintype "passive"))
    )
    (net (code "40") (name "/LO2") (class "Default")
      (node (ref "R12") (pin "1") (pinfunction "1_1") (pintype "passive"))
      (node (ref "U5") (pin "15") (pinfunction "LO2_15") (pintype "passive"))
    )
    (net (code "41") (name "/LO3") (class "Default")
      (node (ref "R13") (pin "1") (pinfunction "1_1") (pintype "passive"))
      (node (ref "U5") (pin "14") (pinfunction "LO3_14") (pintype "passive"))
    )
    (net (code "42") (name "/PWR_AD") (class "Default")
      (node (ref "R29") (pin "2") (pinfunction "2_2") (pintype "passive"))
      (node (ref "U6") (pin "9") (pinfunction "PC1_9") (pintype "passive"))
    )
    (net (code "43") (name "/SWCLK") (class "Default")
      (node (ref "J3") (pin "3") (pinfunction "3_3") (pintype "passive"))
      (node (ref "U6") (pin "49") (pinfunction "PA14_49") (pintype "passive"))
    )
    (net (code "44") (name "/SWDIO") (class "Default")
      (node (ref "J3") (pin "2") (pinfunction "2_2") (pintype "passive"))
      (node (ref "U6") (pin "46") (pinfunction "PA13_46") (pintype "passive"))
    )
    (net (code "45") (name "/S_SCL") (class "Default")
      (node (ref "U6") (pin "29") (pinfunction "PB10_29") (pintype "passive"))
    )
    (net (code "46") (name "/S_SDA") (class "Default")
      (node (ref "U6") (pin "30") (pinfunction "PB11_30") (pintype "passive"))
    )
    (net (code "47") (name "/Sensor_A") (class "Default")
      (node (ref "U6") (pin "25") (pinfunction "PC5_25") (pintype "passive"))
    )
    (net (code "48") (name "/TEMP") (class "Default")
      (node (ref "C22") (pin "2") (pinfunction "2_2") (pintype "passive"))
      (node (ref "R27") (pin "1") (pinfunction "1_1") (pintype "passive"))
      (node (ref "R30") (pin "2") (pinfunction "2_2") (pintype "passive"))
      (node (ref "U6") (pin "10") (pinfunction "PC2_10") (pintype "passive"))
    )
    (net (code "49") (name "/U") (class "Default")
      (node (ref "C16") (pin "1") (pinfunction "1_1") (pintype "passive"))
      (node (ref "J2") (pin "1") (pinfunction "1_1") (pintype "passive"))
      (node (ref "Q1") (pin "S") (pinfunction "S_S") (pintype "passive"))
      (node (ref "Q4") (pin "D") (pinfunction "D_D") (pintype "passive"))
      (node (ref "R8") (pin "2") (pinfunction "2_2") (pintype "passive"))
      (node (ref "U5") (pin "26") (pinfunction "VS1_26") (pintype "passive"))
    )
    (net (code "50") (name "/UN") (class "Default")
      (node (ref "C25") (pin "2") (pinfunction "2_2") (pintype "passive"))
      (node (ref "R23") (pin "1") (pinfunction "1_1") (pintype "passive"))
      (node (ref "R34") (pin "1") (pinfunction "1_1") (pintype "passive"))
    )
    (net (code "51") (name "/UP") (class "Default")
      (node (ref "C25") (pin "1") (pinfunction "1_1") (pintype "passive"))
      (node (ref "R20") (pin "1") (pinfunction "1_1") (pintype "passive"))
      (node (ref "R37") (pin "1") (pinfunction "1_1") (pintype "passive"))
    )
    (net (code "52") (name "/V") (class "Default")
      (node (ref "C15") (pin "1") (pinfunction "1_1") (pintype "passive"))
      (node (ref "J2") (pin "2") (pinfunction "2_2") (pintype "passive"))
      (node (ref "Q2") (pin "S") (pinfunction "S_S") (pintype "passive"))
      (node (ref "Q5") (pin "D") (pinfunction "D_D") (pintype "passive"))
      (node (ref "R9") (pin "2") (pinfunction "2_2") (pintype "passive"))
      (node (ref "U5") (pin "22") (pinfunction "VS2_22") (pintype "passive"))
    )
    (net (code "53") (name "/VN") (class "Default")
      (node (ref "C30") (pin "2") (pinfunction "2_2") (pintype "passive"))
      (node (ref "R24") (pin "1") (pinfunction "1_1") (pintype "passive"))
      (node (ref "R43") (pin "1") (pinfunction "1_1") (pintype "passive"))
    )
    (net (code "54") (name "/VP") (class "Default")
      (node (ref "C30") (pin "1") (pinfunction "1_1") (pintype "passive"))
      (node (ref "R21") (pin "1") (pinfunction "1_1") (pintype "passive"))
      (node (ref "R47") (pin "1") (pinfunction "1_1") (pintype "passive"))
    )
    (net (code "55") (name "/W") (class "Default")
      (node (ref "C2") (pin "1") (pinfunction "1_1") (pintype "passive"))
      (node (ref "J2") (pin "3") (pinfunction "3_3") (pintype "passive"))
      (node (ref "Q3") (pin "S") (pinfunction "S_S") (pintype "passive"))
      (node (ref "Q6") (pin "D") (pinfunction "D_D") (pintype "passive"))
      (node (ref "R10") (pin "2") (pinfunction "2_2") (pintype "passive"))
      (node (ref "U5") (pin "18") (pinfunction "VS3_18") (pintype "passive"))
    )
    (net (code "56") (name "/WN") (class "Default")
      (node (ref "C29") (pin "2") (pinfunction "2_2") (pintype "passive"))
      (node (ref "R25") (pin "1") (pinfunction "1_1") (pintype "passive"))
      (node (ref "R42") (pin "1") (pinfunction "1_1") (pintype "passive"))
    )
    (net (code "57") (name "/WP") (class "Default")
      (node (ref "C29") (pin "1") (pinfunction "1_1") (pintype "passive"))
      (node (ref "R22") (pin "1") (pinfunction "1_1") (pintype "passive"))
      (node (ref "R46") (pin "1") (pinfunction "1_1") (pintype "passive"))
    )
    (net (code "58") (name "AGND") (class "Default")
      (node (ref "C22") (pin "1") (pinfunction "1_1") (pintype "passive"))
      (node (ref "C23") (pin "1") (pinfunction "1_1") (pintype "passive"))
      (node (ref "C24") (pin "1") (pinfunction "1_1") (pintype "passive"))
      (node (ref "C26") (pin "1") (pinfunction "1_1") (pintype "passive"))
      (node (ref "C27") (pin "1") (pinfunction "1_1") (pintype "passive"))
      (node (ref "C28") (pin "1") (pinfunction "1_1") (pintype "passive"))
      (node (ref "C31") (pin "1") (pinfunction "1_1") (pintype "passive"))
      (node (ref "C32") (pin "1") (pinfunction "1_1") (pintype "passive"))
      (node (ref "L2") (pin "2") (pinfunction "2_2") (pintype "passive"))
      (node (ref "R30") (pin "1") (pinfunction "1_1") (pintype "passive"))
      (node (ref "R31") (pin "1") (pinfunction "1_1") (pintype "passive"))
      (node (ref "R38") (pin "2") (pinfunction "2_2") (pintype "passive"))
      (node (ref "U4") (pin "11") (pinfunction "gnd_11") (pintype "passive"))
    )
    (net (code "59") (name "DGND") (class "Default")
      (node (ref "C13") (pin "1") (pinfunction "1_1") (pintype "passive"))
      (node (ref "C14") (pin "1") (pinfunction "1_1") (pintype "passive"))
      (node (ref "C33") (pin "1") (pinfunction "1_1") (pintype "passive"))
      (node (ref "C34") (pin "1") (pinfunction "1_1") (pintype "passive"))
      (node (ref "C35") (pin "1") (pinfunction "1_1") (pintype "passive"))
      (node (ref "C36") (pin "1") (pinfunction "1_1") (pintype "passive"))
      (node (ref "C37") (pin "1") (pinfunction "1_1") (pintype "passive"))
      (node (ref "C38") (pin "1") (pinfunction "1_1") (pintype "passive"))
      (node (ref "C39") (pin "1") (pinfunction "1_1") (pintype "passive"))
      (node (ref "C42") (pin "2") (pinfunction "2_2") (pintype "passive"))
      (node (ref "C43") (pin "1") (pinfunction "1_1") (pintype "passive"))
      (node (ref "C44") (pin "1") (pinfunction "1_1") (pintype "passive"))
      (node (ref "C45") (pin "1") (pinfunction "1_1") (pintype "passive"))
      (node (ref "C46") (pin "1") (pinfunction "1_1") (pintype "passive"))
      (node (ref "C47") (pin "1") (pinfunction "1_1") (pintype "passive"))
      (node (ref "J3") (pin "1") (pinfunction "1_1") (pintype "passive"))
      (node (ref "J4") (pin "1") (pinfunction "1_1") (pintype "passive"))
      (node (ref "R26") (pin "2") (pinfunction "2_2") (pintype "passive"))
      (node (ref "R51") (pin "2") (pinfunction "2_2") (pintype "passive"))
      (node (ref "R52") (pin "1") (pinfunction "1_1") (pintype "passive"))
      (node (ref "R57") (pin "1") (pinfunction "1_1") (pintype "passive"))
      (node (ref "R58") (pin "2") (pinfunction "2_2") (pintype "passive"))
      (node (ref "R59") (pin "2") (pinfunction "2_2") (pintype "passive"))
      (node (ref "S1") (pin "2") (pinfunction "2_2") (pintype "passive"))
      (node (ref "T3") (pin "1") (pinfunction "GND_1") (pintype "passive"))
      (node (ref "T4") (pin "1") (pinfunction "GND_1") (pintype "passive"))
      (node (ref "U6") (pin "18") (pinfunction "VSS_18") (pintype "passive"))
      (node (ref "U6") (pin "63") (pinfunction "VSS_63") (pintype "passive"))
      (node (ref "U8") (pin "3") (pinfunction "GND_3") (pintype "passive"))
      (node (ref "X1") (pin "3") (pinfunction "gnd_3") (pintype "passive"))
    )
    (net (code "60") (name "GND") (class "Default")
      (node (ref "C1") (pin "2") (pinfunction "2_2") (pintype "passive"))
      (node (ref "C10") (pin "1") (pinfunction "1_1") (pintype "passive"))
      (node (ref "C11") (pin "1") (pinfunction "1_1") (pintype "passive"))
      (node (ref "C12") (pin "1") (pinfunction "1_1") (pintype "passive"))
      (node (ref "C17") (pin "1") (pinfunction "1_1") (pintype "passive"))
      (node (ref "C18") (pin "1") (pinfunction "1_1") (pintype "passive"))
      (node (ref "C3") (pin "1") (pinfunction "1_1") (pintype "passive"))
      (node (ref "C4") (pin "1") (pinfunction "1_1") (pintype "passive"))
      (node (ref "C5") (pin "2") (pinfunction "2_2") (pintype "passive"))
      (node (ref "C52") (pin "1") (pinfunction "1_1") (pintype "passive"))
      (node (ref "C7") (pin "1") (pinfunction "1_1") (pintype "passive"))
      (node (ref "C8") (pin "1") (pinfunction "1_1") (pintype "passive"))
      (node (ref "C9") (pin "1") (pinfunction "1_1") (pintype "passive"))
      (node (ref "D1") (pin "1") (pinfunction "A_1") (pintype "passive"))
      (node (ref "J1") (pin "1") (pinfunction "1_1") (pintype "passive"))
      (node (ref "L2") (pin "1") (pinfunction "1_1") (pintype "passive"))
      (node (ref "R17") (pin "1") (pinfunction "1_1") (pintype "passive"))
      (node (ref "R18") (pin "1") (pinfunction "1_1") (pintype "passive"))
      (node (ref "R19") (pin "1") (pinfunction "1_1") (pintype "passive"))
      (node (ref "R23") (pin "2") (pinfunction "2_2") (pintype "passive"))
      (node (ref "R24") (pin "2") (pinfunction "2_2") (pintype "passive"))
      (node (ref "R25") (pin "2") (pinfunction "2_2") (pintype "passive"))
      (node (ref "R26") (pin "1") (pinfunction "1_1") (pintype "passive"))
      (node (ref "R3") (pin "1") (pinfunction "1_1") (pintype "passive"))
      (node (ref "R4") (pin "2") (pinfunction "2_2") (pintype "passive"))
      (node (ref "R58") (pin "1") (pinfunction "1_1") (pintype "passive"))
      (node (ref "R59") (pin "1") (pinfunction "1_1") (pintype "passive"))
      (node (ref "U1") (pin "2") (pinfunction "GND_2") (pintype "passive"))
      (node (ref "U2") (pin "1") (pinfunction "GND_1") (pintype "passive"))
      (node (ref "U3") (pin "2") (pinfunction "GND_2") (pintype "passive"))
      (node (ref "U5") (pin "12") (pinfunction "VSS_12") (pintype "passive"))
      (node (ref "U5") (pin "13") (pinfunction "COM_13") (pintype "passive"))
      (node (ref "U7") (pin "0") (pinfunction "0_0") (pintype "passive"))
      (node (ref "U7") (pin "A1") (pinfunction "GND_A1") (pintype "passive"))
      (node (ref "U7") (pin "A12") (pinfunction "GND_A12") (pintype "passive"))
      (node (ref "U7") (pin "B1") (pinfunction "GND_B1") (pintype "passive"))
      (node (ref "U7") (pin "B12") (pinfunction "GND_B12") (pintype "passive"))
    )
    (net (code "61") (name "Net-(C23-Pad2)") (class "Default")
      (node (ref "C23") (pin "2") (pinfunction "2_2") (pintype "passive"))
      (node (ref "R28") (pin "1") (pinfunction "1_1") (pintype "passive"))
      (node (ref "R29") (pin "1") (pinfunction "1_1") (pintype "passive"))
      (node (ref "R31") (pin "2") (pinfunction "2_2") (pintype "passive"))
    )
    (net (code "62") (name "Net-(D1-K)") (class "Default")
      (node (ref "C6") (pin "2") (pinfunction "2_2") (pintype "passive"))
      (node (ref "D1") (pin "2") (pinfunction "K_2") (pintype "passive"))
      (node (ref "L1") (pin "1") (pinfunction "1_1") (pintype "passive"))
      (node (ref "U1") (pin "6") (pinfunction "SW_6") (pintype "passive"))
    )
    (net (code "63") (name "Net-(D2-K)") (class "Default")
      (node (ref "D2") (pin "2") (pinfunction "K_2") (pintype "passive"))
      (node (ref "R4") (pin "1") (pinfunction "1_1") (pintype "passive"))
    )
    (net (code "64") (name "Net-(D3-K)") (class "Default")
      (node (ref "C2") (pin "2") (pinfunction "2_2") (pintype "passive"))
      (node (ref "D3") (pin "2") (pinfunction "K_2") (pintype "passive"))
      (node (ref "U5") (pin "20") (pinfunction "VB3_20") (pintype "passive"))
    )
    (net (code "65") (name "Net-(D4-K)") (class "Default")
      (node (ref "C15") (pin "2") (pinfunction "2_2") (pintype "passive"))
      (node (ref "D4") (pin "2") (pinfunction "K_2") (pintype "passive"))
      (node (ref "U5") (pin "24") (pinfunction "VB2_24") (pintype "passive"))
    )
    (net (code "66") (name "Net-(D5-K)") (class "Default")
      (node (ref "C16") (pin "2") (pinfunction "2_2") (pintype "passive"))
      (node (ref "D5") (pin "2") (pinfunction "K_2") (pintype "passive"))
      (node (ref "U5") (pin "28") (pinfunction "VB1_28") (pintype "passive"))
    )
    (net (code "67") (name "Net-(F1-GND-Pad1)") (class "Default")
      (node (ref "F1") (pin "1") (pinfunction "GND_1") (pintype "passive"))
      (node (ref "J1") (pin "2") (pinfunction "2_2") (pintype "passive"))
    )
    (net (code "68") (name "Net-(J4-Pad3)") (class "Default")
      (node (ref "J4") (pin "3") (pinfunction "3_3") (pintype "passive"))
      (node (ref "RN1") (pin "4") (pinfunction "4_4") (pintype "passive"))
      (node (ref "RN2") (pin "4") (pinfunction "4_4") (pintype "passive"))
    )
    (net (code "69") (name "Net-(J4-Pad4)") (class "Default")
      (node (ref "J4") (pin "4") (pinfunction "4_4") (pintype "passive"))
      (node (ref "RN1") (pin "2") (pinfunction "2_2") (pintype "passive"))
      (node (ref "RN2") (pin "3") (pinfunction "3_3") (pintype "passive"))
    )
    (net (code "70") (name "Net-(J4-Pad5)") (class "Default")
      (node (ref "J4") (pin "5") (pinfunction "5_5") (pintype "passive"))
      (node (ref "RN1") (pin "1") (pinfunction "1_1") (pintype "passive"))
      (node (ref "RN2") (pin "2") (pinfunction "2_2") (pintype "passive"))
    )
    (net (code "71") (name "Net-(Q1-PadG)") (class "Default")
      (node (ref "Q1") (pin "G") (pinfunction "G_G") (pintype "passive"))
      (node (ref "R5") (pin "2") (pinfunction "2_2") (pintype "passive"))
      (node (ref "R8") (pin "1") (pinfunction "1_1") (pintype "passive"))
    )
    (net (code "72") (name "Net-(Q2-PadG)") (class "Default")
      (node (ref "Q2") (pin "G") (pinfunction "G_G") (pintype "passive"))
      (node (ref "R6") (pin "2") (pinfunction "2_2") (pintype "passive"))
      (node (ref "R9") (pin "1") (pinfunction "1_1") (pintype "passive"))
    )
    (net (code "73") (name "Net-(Q3-PadG)") (class "Default")
      (node (ref "Q3") (pin "G") (pinfunction "G_G") (pintype "passive"))
      (node (ref "R10") (pin "1") (pinfunction "1_1") (pintype "passive"))
      (node (ref "R7") (pin "2") (pinfunction "2_2") (pintype "passive"))
    )
    (net (code "74") (name "Net-(Q4-PadG)") (class "Default")
      (node (ref "Q4") (pin "G") (pinfunction "G_G") (pintype "passive"))
      (node (ref "R11") (pin "2") (pinfunction "2_2") (pintype "passive"))
      (node (ref "R14") (pin "1") (pinfunction "1_1") (pintype "passive"))
    )
    (net (code "75") (name "Net-(Q4-PadS)") (class "Default")
      (node (ref "Q4") (pin "S") (pinfunction "S_S") (pintype "passive"))
      (node (ref "R14") (pin "2") (pinfunction "2_2") (pintype "passive"))
      (node (ref "R17") (pin "2") (pinfunction "2_2") (pintype "passive"))
      (node (ref "R20") (pin "2") (pinfunction "2_2") (pintype "passive"))
    )
    (net (code "76") (name "Net-(Q5-PadG)") (class "Default")
      (node (ref "Q5") (pin "G") (pinfunction "G_G") (pintype "passive"))
      (node (ref "R12") (pin "2") (pinfunction "2_2") (pintype "passive"))
      (node (ref "R15") (pin "1") (pinfunction "1_1") (pintype "passive"))
    )
    (net (code "77") (name "Net-(Q5-PadS)") (class "Default")
      (node (ref "Q5") (pin "S") (pinfunction "S_S") (pintype "passive"))
      (node (ref "R15") (pin "2") (pinfunction "2_2") (pintype "passive"))
      (node (ref "R18") (pin "2") (pinfunction "2_2") (pintype "passive"))
      (node (ref "R21") (pin "2") (pinfunction "2_2") (pintype "passive"))
    )
    (net (code "78") (name "Net-(Q6-PadG)") (class "Default")
      (node (ref "Q6") (pin "G") (pinfunction "G_G") (pintype "passive"))
      (node (ref "R13") (pin "2") (pinfunction "2_2") (pintype "passive"))
      (node (ref "R16") (pin "1") (pinfunction "1_1") (pintype "passive"))
    )
    (net (code "79") (name "Net-(Q6-PadS)") (class "Default")
      (node (ref "Q6") (pin "S") (pinfunction "S_S") (pintype "passive"))
      (node (ref "R16") (pin "2") (pinfunction "2_2") (pintype "passive"))
      (node (ref "R19") (pin "2") (pinfunction "2_2") (pintype "passive"))
      (node (ref "R22") (pin "2") (pinfunction "2_2") (pintype "passive"))
    )
    (net (code "80") (name "Net-(T1-GND)") (class "Default")
      (node (ref "R53") (pin "1") (pinfunction "1_1") (pintype "passive"))
      (node (ref "T1") (pin "1") (pinfunction "GND_1") (pintype "passive"))
    )
    (net (code "81") (name "Net-(T2-GND)") (class "Default")
      (node (ref "R54") (pin "1") (pinfunction "1_1") (pintype "passive"))
      (node (ref "T2") (pin "1") (pinfunction "GND_1") (pintype "passive"))
    )
    (net (code "82") (name "Net-(U1-BST)") (class "Default")
      (node (ref "C6") (pin "1") (pinfunction "1_1") (pintype "passive"))
      (node (ref "U1") (pin "1") (pinfunction "BST_1") (pintype "passive"))
    )
    (net (code "83") (name "Net-(U1-EN)") (class "Default")
      (node (ref "R1") (pin "1") (pinfunction "1_1") (pintype "passive"))
      (node (ref "U1") (pin "4") (pinfunction "EN_4") (pintype "passive"))
    )
    (net (code "84") (name "Net-(U4A-+)") (class "Default")
      (node (ref "C28") (pin "2") (pinfunction "2_2") (pintype "passive"))
      (node (ref "R33") (pin "2") (pinfunction "2_2") (pintype "passive"))
      (node (ref "R38") (pin "1") (pinfunction "1_1") (pintype "passive"))
      (node (ref "U4") (pin "3") (pinfunction "+_3") (pintype "passive"))
    )
    (net (code "85") (name "Net-(U4A--)") (class "Default")
      (node (ref "R35") (pin "1") (pinfunction "1_1") (pintype "passive"))
      (node (ref "U4") (pin "1") (pinfunction "OUT_1") (pintype "passive"))
      (node (ref "U4") (pin "2") (pinfunction "-_2") (pintype "passive"))
    )
    (net (code "86") (name "Net-(U4B-+)") (class "Default")
      (node (ref "R37") (pin "2") (pinfunction "2_2") (pintype "passive"))
      (node (ref "R39") (pin "2") (pinfunction "2_2") (pintype "passive"))
      (node (ref "U4") (pin "5") (pinfunction "+_5") (pintype "passive"))
    )
    (net (code "87") (name "Net-(U4B--)") (class "Default")
      (node (ref "R32") (pin "2") (pinfunction "2_2") (pintype "passive"))
      (node (ref "R34") (pin "2") (pinfunction "2_2") (pintype "passive"))
      (node (ref "U4") (pin "6") (pinfunction "-_6") (pintype "passive"))
    )
    (net (code "88") (name "Net-(U4B-OUT)") (class "Default")
      (node (ref "R32") (pin "1") (pinfunction "1_1") (pintype "passive"))
      (node (ref "R36") (pin "2") (pinfunction "2_2") (pintype "passive"))
      (node (ref "U4") (pin "7") (pinfunction "OUT_7") (pintype "passive"))
    )
    (net (code "89") (name "Net-(U4C-+)") (class "Default")
      (node (ref "R47") (pin "2") (pinfunction "2_2") (pintype "passive"))
      (node (ref "R49") (pin "2") (pinfunction "2_2") (pintype "passive"))
      (node (ref "U4") (pin "10") (pinfunction "+_10") (pintype "passive"))
    )
    (net (code "90") (name "Net-(U4C--)") (class "Default")
      (node (ref "R41") (pin "2") (pinfunction "2_2") (pintype "passive"))
      (node (ref "R43") (pin "2") (pinfunction "2_2") (pintype "passive"))
      (node (ref "U4") (pin "9") (pinfunction "-_9") (pintype "passive"))
    )
    (net (code "91") (name "Net-(U4C-OUT)") (class "Default")
      (node (ref "R41") (pin "1") (pinfunction "1_1") (pintype "passive"))
      (node (ref "R45") (pin "2") (pinfunction "2_2") (pintype "passive"))
      (node (ref "U4") (pin "8") (pinfunction "OUT_8") (pintype "passive"))
    )
    (net (code "92") (name "Net-(U4D-+)") (class "Default")
      (node (ref "R46") (pin "2") (pinfunction "2_2") (pintype "passive"))
      (node (ref "R48") (pin "2") (pinfunction "2_2") (pintype "passive"))
      (node (ref "U4") (pin "12") (pinfunction "+_12") (pintype "passive"))
    )
    (net (code "93") (name "Net-(U4D--)") (class "Default")
      (node (ref "R40") (pin "2") (pinfunction "2_2") (pintype "passive"))
      (node (ref "R42") (pin "2") (pinfunction "2_2") (pintype "passive"))
      (node (ref "U4") (pin "13") (pinfunction "-_13") (pintype "passive"))
    )
    (net (code "94") (name "Net-(U4D-OUT)") (class "Default")
      (node (ref "R40") (pin "1") (pinfunction "1_1") (pintype "passive"))
      (node (ref "R44") (pin "2") (pinfunction "2_2") (pintype "passive"))
      (node (ref "U4") (pin "14") (pinfunction "OUT_14") (pintype "passive"))
    )
    (net (code "95") (name "Net-(U5-EN)") (class "Default")
      (node (ref "R60") (pin "1") (pinfunction "1_1") (pintype "passive"))
      (node (ref "U5") (pin "10") (pinfunction "EN_10") (pintype "passive"))
    )
    (net (code "96") (name "Net-(U5-HIN1)") (class "Default")
      (node (ref "RN3") (pin "4") (pinfunction "4_4") (pintype "passive"))
      (node (ref "U5") (pin "2") (pinfunction "HIN1_2") (pintype "passive"))
    )
    (net (code "97") (name "Net-(U5-HIN2)") (class "Default")
      (node (ref "RN3") (pin "3") (pinfunction "3_3") (pintype "passive"))
      (node (ref "U5") (pin "3") (pinfunction "HIN2_3") (pintype "passive"))
    )
    (net (code "98") (name "Net-(U5-HIN3)") (class "Default")
      (node (ref "RN3") (pin "2") (pinfunction "2_2") (pintype "passive"))
      (node (ref "U5") (pin "4") (pinfunction "HIN3_4") (pintype "passive"))
    )
    (net (code "99") (name "Net-(U5-ITRIP)") (class "Default")
      (node (ref "R57") (pin "2") (pinfunction "2_2") (pintype "passive"))
      (node (ref "U5") (pin "9") (pinfunction "ITRIP_9") (pintype "passive"))
    )
    (net (code "100") (name "Net-(U5-LIN1)") (class "Default")
      (node (ref "RN3") (pin "1") (pinfunction "1_1") (pintype "passive"))
      (node (ref "U5") (pin "5") (pinfunction "LIN1_5") (pintype "passive"))
    )
    (net (code "101") (name "Net-(U5-LIN2)") (class "Default")
      (node (ref "RN4") (pin "4") (pinfunction "4_4") (pintype "passive"))
      (node (ref "U5") (pin "6") (pinfunction "LIN2_6") (pintype "passive"))
    )
    (net (code "102") (name "Net-(U5-LIN3)") (class "Default")
      (node (ref "RN4") (pin "3") (pinfunction "3_3") (pintype "passive"))
      (node (ref "U5") (pin "7") (pinfunction "LIN3_7") (pintype "passive"))
    )
    (net (code "103") (name "Net-(U5-RCIN)") (class "Default")
      (node (ref "C17") (pin "2") (pinfunction "2_2") (pintype "passive"))
      (node (ref "R61") (pin "1") (pinfunction "1_1") (pintype "passive"))
      (node (ref "U5") (pin "11") (pinfunction "RCIN_11") (pintype "passive"))
    )
    (net (code "104") (name "Net-(U6-BOOT0)") (class "Default")
      (node (ref "R51") (pin "1") (pinfunction "1_1") (pintype "passive"))
      (node (ref "U6") (pin "60") (pinfunction "BOOT0_60") (pintype "passive"))
    )
    (net (code "105") (name "Net-(U6-NRST)") (class "Default")
      (node (ref "C33") (pin "2") (pinfunction "2_2") (pintype "passive"))
      (node (ref "R50") (pin "1") (pinfunction "1_1") (pintype "passive"))
      (node (ref "S1") (pin "1") (pinfunction "1_1") (pintype "passive"))
      (node (ref "U6") (pin "7") (pinfunction "NRST_7") (pintype "passive"))
    )
    (net (code "106") (name "Net-(U6-PA4)") (class "Default")
      (node (ref "R53") (pin "2") (pinfunction "2_2") (pintype "passive"))
      (node (ref "U6") (pin "20") (pinfunction "PA4_20") (pintype "passive"))
    )
    (net (code "107") (name "Net-(U6-PA5)") (class "Default")
      (node (ref "R54") (pin "2") (pinfunction "2_2") (pintype "passive"))
      (node (ref "U6") (pin "21") (pinfunction "PA5_21") (pintype "passive"))
    )
    (net (code "108") (name "Net-(U6-PH0)") (class "Default")
      (node (ref "U6") (pin "5") (pinfunction "PH0_5") (pintype "passive"))
      (node (ref "X1") (pin "1") (pinfunction "1_1") (pintype "passive"))
    )
    (net (code "109") (name "Net-(U6-PH1)") (class "Default")
      (node (ref "U6") (pin "6") (pinfunction "PH1_6") (pintype "passive"))
      (node (ref "X1") (pin "2") (pinfunction "2_2") (pintype "passive"))
    )
    (net (code "110") (name "Net-(U6-VSSA)") (class "Default")
      (node (ref "R52") (pin "2") (pinfunction "2_2") (pintype "passive"))
      (node (ref "U6") (pin "12") (pinfunction "VSSA_12") (pintype "passive"))
    )
    (net (code "111") (name "Net-(U8-V3)") (class "Default")
      (node (ref "C43") (pin "2") (pinfunction "2_2") (pintype "passive"))
      (node (ref "U8") (pin "8") (pinfunction "V3_8") (pintype "passive"))
    )
    (net (code "112") (name "PWR") (class "Default")
      (node (ref "C1") (pin "1") (pinfunction "1_1") (pintype "passive"))
      (node (ref "C3") (pin "2") (pinfunction "2_2") (pintype "passive"))
      (node (ref "C4") (pin "2") (pinfunction "2_2") (pintype "passive"))
      (node (ref "C5") (pin "1") (pinfunction "1_1") (pintype "passive"))
      (node (ref "C7") (pin "2") (pinfunction "2_2") (pintype "passive"))
      (node (ref "F1") (pin "2") (pinfunction "GND_2") (pintype "passive"))
      (node (ref "Q1") (pin "D") (pinfunction "D_D") (pintype "passive"))
      (node (ref "Q2") (pin "D") (pinfunction "D_D") (pintype "passive"))
      (node (ref "Q3") (pin "D") (pinfunction "D_D") (pintype "passive"))
      (node (ref "R1") (pin "2") (pinfunction "2_2") (pintype "passive"))
      (node (ref "R28") (pin "2") (pinfunction "2_2") (pintype "passive"))
      (node (ref "U1") (pin "5") (pinfunction "VIN_5") (pintype "passive"))
    )
    (net (code "113") (name "VCC") (class "Default")
      (node (ref "C13") (pin "2") (pinfunction "2_2") (pintype "passive"))
      (node (ref "C14") (pin "2") (pinfunction "2_2") (pintype "passive"))
      (node (ref "C24") (pin "2") (pinfunction "2_2") (pintype "passive"))
      (node (ref "C34") (pin "2") (pinfunction "2_2") (pintype "passive"))
      (node (ref "C35") (pin "2") (pinfunction "2_2") (pintype "passive"))
      (node (ref "C36") (pin "2") (pinfunction "2_2") (pintype "passive"))
      (node (ref "C37") (pin "2") (pinfunction "2_2") (pintype "passive"))
      (node (ref "C38") (pin "2") (pinfunction "2_2") (pintype "passive"))
      (node (ref "C39") (pin "2") (pinfunction "2_2") (pintype "passive"))
      (node (ref "D2") (pin "1") (pinfunction "A_1") (pintype "passive"))
      (node (ref "J3") (pin "4") (pinfunction "4_4") (pintype "passive"))
      (node (ref "R27") (pin "2") (pinfunction "2_2") (pintype "passive"))
      (node (ref "R33") (pin "1") (pinfunction "1_1") (pintype "passive"))
      (node (ref "R50") (pin "2") (pinfunction "2_2") (pintype "passive"))
      (node (ref "RN2") (pin "5") (pinfunction "5_5") (pintype "passive"))
      (node (ref "RN2") (pin "6") (pinfunction "6_6") (pintype "passive"))
      (node (ref "RN2") (pin "7") (pinfunction "7_7") (pintype "passive"))
      (node (ref "U3") (pin "5") (pinfunction "OUT_5") (pintype "passive"))
      (node (ref "U4") (pin "4") (pinfunction "4_4") (pintype "passive"))
      (node (ref "U6") (pin "1") (pinfunction "VBAT_1") (pintype "passive"))
      (node (ref "U6") (pin "13") (pinfunction "VDDA_13") (pintype "passive"))
      (node (ref "U6") (pin "19") (pinfunction "VDD_19") (pintype "passive"))
      (node (ref "U6") (pin "32") (pinfunction "VDD_32") (pintype "passive"))
      (node (ref "U6") (pin "48") (pinfunction "VDD_48") (pintype "passive"))
      (node (ref "U6") (pin "64") (pinfunction "VDD_64") (pintype "passive"))
    )
    (net (code "114") (name "VUSB") (class "Default")
      (node (ref "C42") (pin "1") (pinfunction "1_1") (pintype "passive"))
      (node (ref "D6") (pin "1") (pinfunction "A_1") (pintype "passive"))
      (node (ref "U7") (pin "A4") (pinfunction "VBUS_A4") (pintype "passive"))
      (node (ref "U7") (pin "A9") (pinfunction "VBUS_A9") (pintype "passive"))
      (node (ref "U7") (pin "B4") (pinfunction "VBUS_B4") (pintype "passive"))
      (node (ref "U7") (pin "B9") (pinfunction "VBUS_B9") (pintype "passive"))
      (node (ref "U8") (pin "5") (pinfunction "VCC_5") (pintype "passive"))
    )
    (net (code "115") (name "unconnected-(RN1-Pad3)") (class "Default")
      (node (ref "RN1") (pin "3") (pinfunction "3_3") (pintype "passive+no_connect"))
    )
    (net (code "116") (name "unconnected-(RN1-Pad6)") (class "Default")
      (node (ref "RN1") (pin "6") (pinfunction "6_6") (pintype "passive+no_connect"))
    )
    (net (code "117") (name "unconnected-(RN2-Pad1)") (class "Default")
      (node (ref "RN2") (pin "1") (pinfunction "1_1") (pintype "passive+no_connect"))
    )
    (net (code "118") (name "unconnected-(RN2-Pad8)") (class "Default")
      (node (ref "RN2") (pin "8") (pinfunction "8_8") (pintype "passive+no_connect"))
    )
    (net (code "119") (name "unconnected-(RN4-Pad1)") (class "Default")
      (node (ref "RN4") (pin "1") (pinfunction "1_1") (pintype "passive+no_connect"))
    )
    (net (code "120") (name "unconnected-(RN4-Pad2)") (class "Default")
      (node (ref "RN4") (pin "2") (pinfunction "2_2") (pintype "passive+no_connect"))
    )
    (net (code "121") (name "unconnected-(RN4-Pad7)") (class "Default")
      (node (ref "RN4") (pin "7") (pinfunction "7_7") (pintype "passive+no_connect"))
    )
    (net (code "122") (name "unconnected-(RN4-Pad8)") (class "Default")
      (node (ref "RN4") (pin "8") (pinfunction "8_8") (pintype "passive+no_connect"))
    )
    (net (code "123") (name "unconnected-(S2-Pad1)") (class "Default")
      (node (ref "S2") (pin "1") (pintype "passive+no_connect"))
    )
    (net (code "124") (name "unconnected-(S3-Pad1)") (class "Default")
      (node (ref "S3") (pin "1") (pintype "passive+no_connect"))
    )
    (net (code "125") (name "unconnected-(S4-Pad1)") (class "Default")
      (node (ref "S4") (pin "1") (pintype "passive+no_connect"))
    )
    (net (code "126") (name "unconnected-(S5-Pad1)") (class "Default")
      (node (ref "S5") (pin "1") (pintype "passive+no_connect"))
    )
    (net (code "127") (name "unconnected-(U3-NC-Pad4)") (class "Default")
      (node (ref "U3") (pin "4") (pinfunction "NC_4") (pintype "passive+no_connect"))
    )
    (net (code "128") (name "unconnected-(U5-FAULT-Pad8)") (class "Default")
      (node (ref "U5") (pin "8") (pinfunction "FAULT_8") (pintype "passive+no_connect"))
    )
    (net (code "129") (name "unconnected-(U5-NC-Pad17)") (class "Default")
      (node (ref "U5") (pin "17") (pinfunction "NC_17") (pintype "passive+no_connect"))
    )
    (net (code "130") (name "unconnected-(U5-NC-Pad21)") (class "Default")
      (node (ref "U5") (pin "21") (pinfunction "NC_21") (pintype "passive+no_connect"))
    )
    (net (code "131") (name "unconnected-(U5-NC-Pad25)") (class "Default")
      (node (ref "U5") (pin "25") (pinfunction "NC_25") (pintype "passive+no_connect"))
    )
    (net (code "132") (name "unconnected-(U6-PA3-Pad17)") (class "Default")
      (node (ref "U6") (pin "17") (pinfunction "PA3_17") (pintype "passive+no_connect"))
    )
    (net (code "133") (name "unconnected-(U6-PB0-Pad26)") (class "Default")
      (node (ref "U6") (pin "26") (pinfunction "PB0_26") (pintype "passive"))
    )
    (net (code "134") (name "unconnected-(U6-PB1-Pad27)") (class "Default")
      (node (ref "U6") (pin "27") (pinfunction "PB1_27") (pintype "passive+no_connect"))
    )
    (net (code "135") (name "unconnected-(U6-PB2-Pad28)") (class "Default")
      (node (ref "U6") (pin "28") (pinfunction "PB2_28") (pintype "passive+no_connect"))
    )
    (net (code "136") (name "unconnected-(U6-PB12-Pad33)") (class "Default")
      (node (ref "U6") (pin "33") (pinfunction "PB12_33") (pintype "passive+no_connect"))
    )
    (net (code "137") (name "unconnected-(U6-PC0-Pad8)") (class "Default")
      (node (ref "U6") (pin "8") (pinfunction "PC0_8") (pintype "passive"))
    )
    (net (code "138") (name "unconnected-(U6-PC3-Pad11)") (class "Default")
      (node (ref "U6") (pin "11") (pinfunction "PC3_11") (pintype "passive"))
    )
    (net (code "139") (name "unconnected-(U6-PC8-Pad39)") (class "Default")
      (node (ref "U6") (pin "39") (pinfunction "PC8_39") (pintype "passive"))
    )
    (net (code "140") (name "unconnected-(U6-PC9-Pad40)") (class "Default")
      (node (ref "U6") (pin "40") (pinfunction "PC9_40") (pintype "passive"))
    )
    (net (code "141") (name "unconnected-(U6-PC14-Pad3)") (class "Default")
      (node (ref "U6") (pin "3") (pinfunction "PC14_3") (pintype "passive+no_connect"))
    )
    (net (code "142") (name "unconnected-(U6-PC15-Pad4)") (class "Default")
      (node (ref "U6") (pin "4") (pinfunction "PC15_4") (pintype "passive+no_connect"))
    )
    (net (code "143") (name "unconnected-(U6-VCAP_1-Pad31)") (class "Default")
      (node (ref "U6") (pin "31") (pinfunction "VCAP_1_31") (pintype "passive+no_connect"))
    )
    (net (code "144") (name "unconnected-(U6-VCAP_2-Pad47)") (class "Default")
      (node (ref "U6") (pin "47") (pinfunction "VCAP_2_47") (pintype "passive+no_connect"))
    )
    (net (code "145") (name "unconnected-(U7-CC1-PadA5)") (class "Default")
      (node (ref "U7") (pin "A5") (pinfunction "CC1_A5") (pintype "passive+no_connect"))
    )
    (net (code "146") (name "unconnected-(U7-CC2-PadB5)") (class "Default")
      (node (ref "U7") (pin "B5") (pinfunction "CC2_B5") (pintype "passive+no_connect"))
    )
    (net (code "147") (name "unconnected-(U7-SBU2-PadB8)") (class "Default")
      (node (ref "U7") (pin "B8") (pinfunction "SBU2_B8") (pintype "passive+no_connect"))
    )
    (net (code "148") (name "unconnected-(U7-SUB1-PadA8)") (class "Default")
      (node (ref "U7") (pin "A8") (pinfunction "SUB1_A8") (pintype "passive+no_connect"))
    )
    (net (code "149") (name "unconnected-(U8-RTS-Pad4)") (class "Default")
      (node (ref "U8") (pin "4") (pinfunction "RTS_4") (pintype "passive+no_connect"))
    )
  )
)
